# MCU.net
KiCad netlist of a schematic drawn in Altium Designer
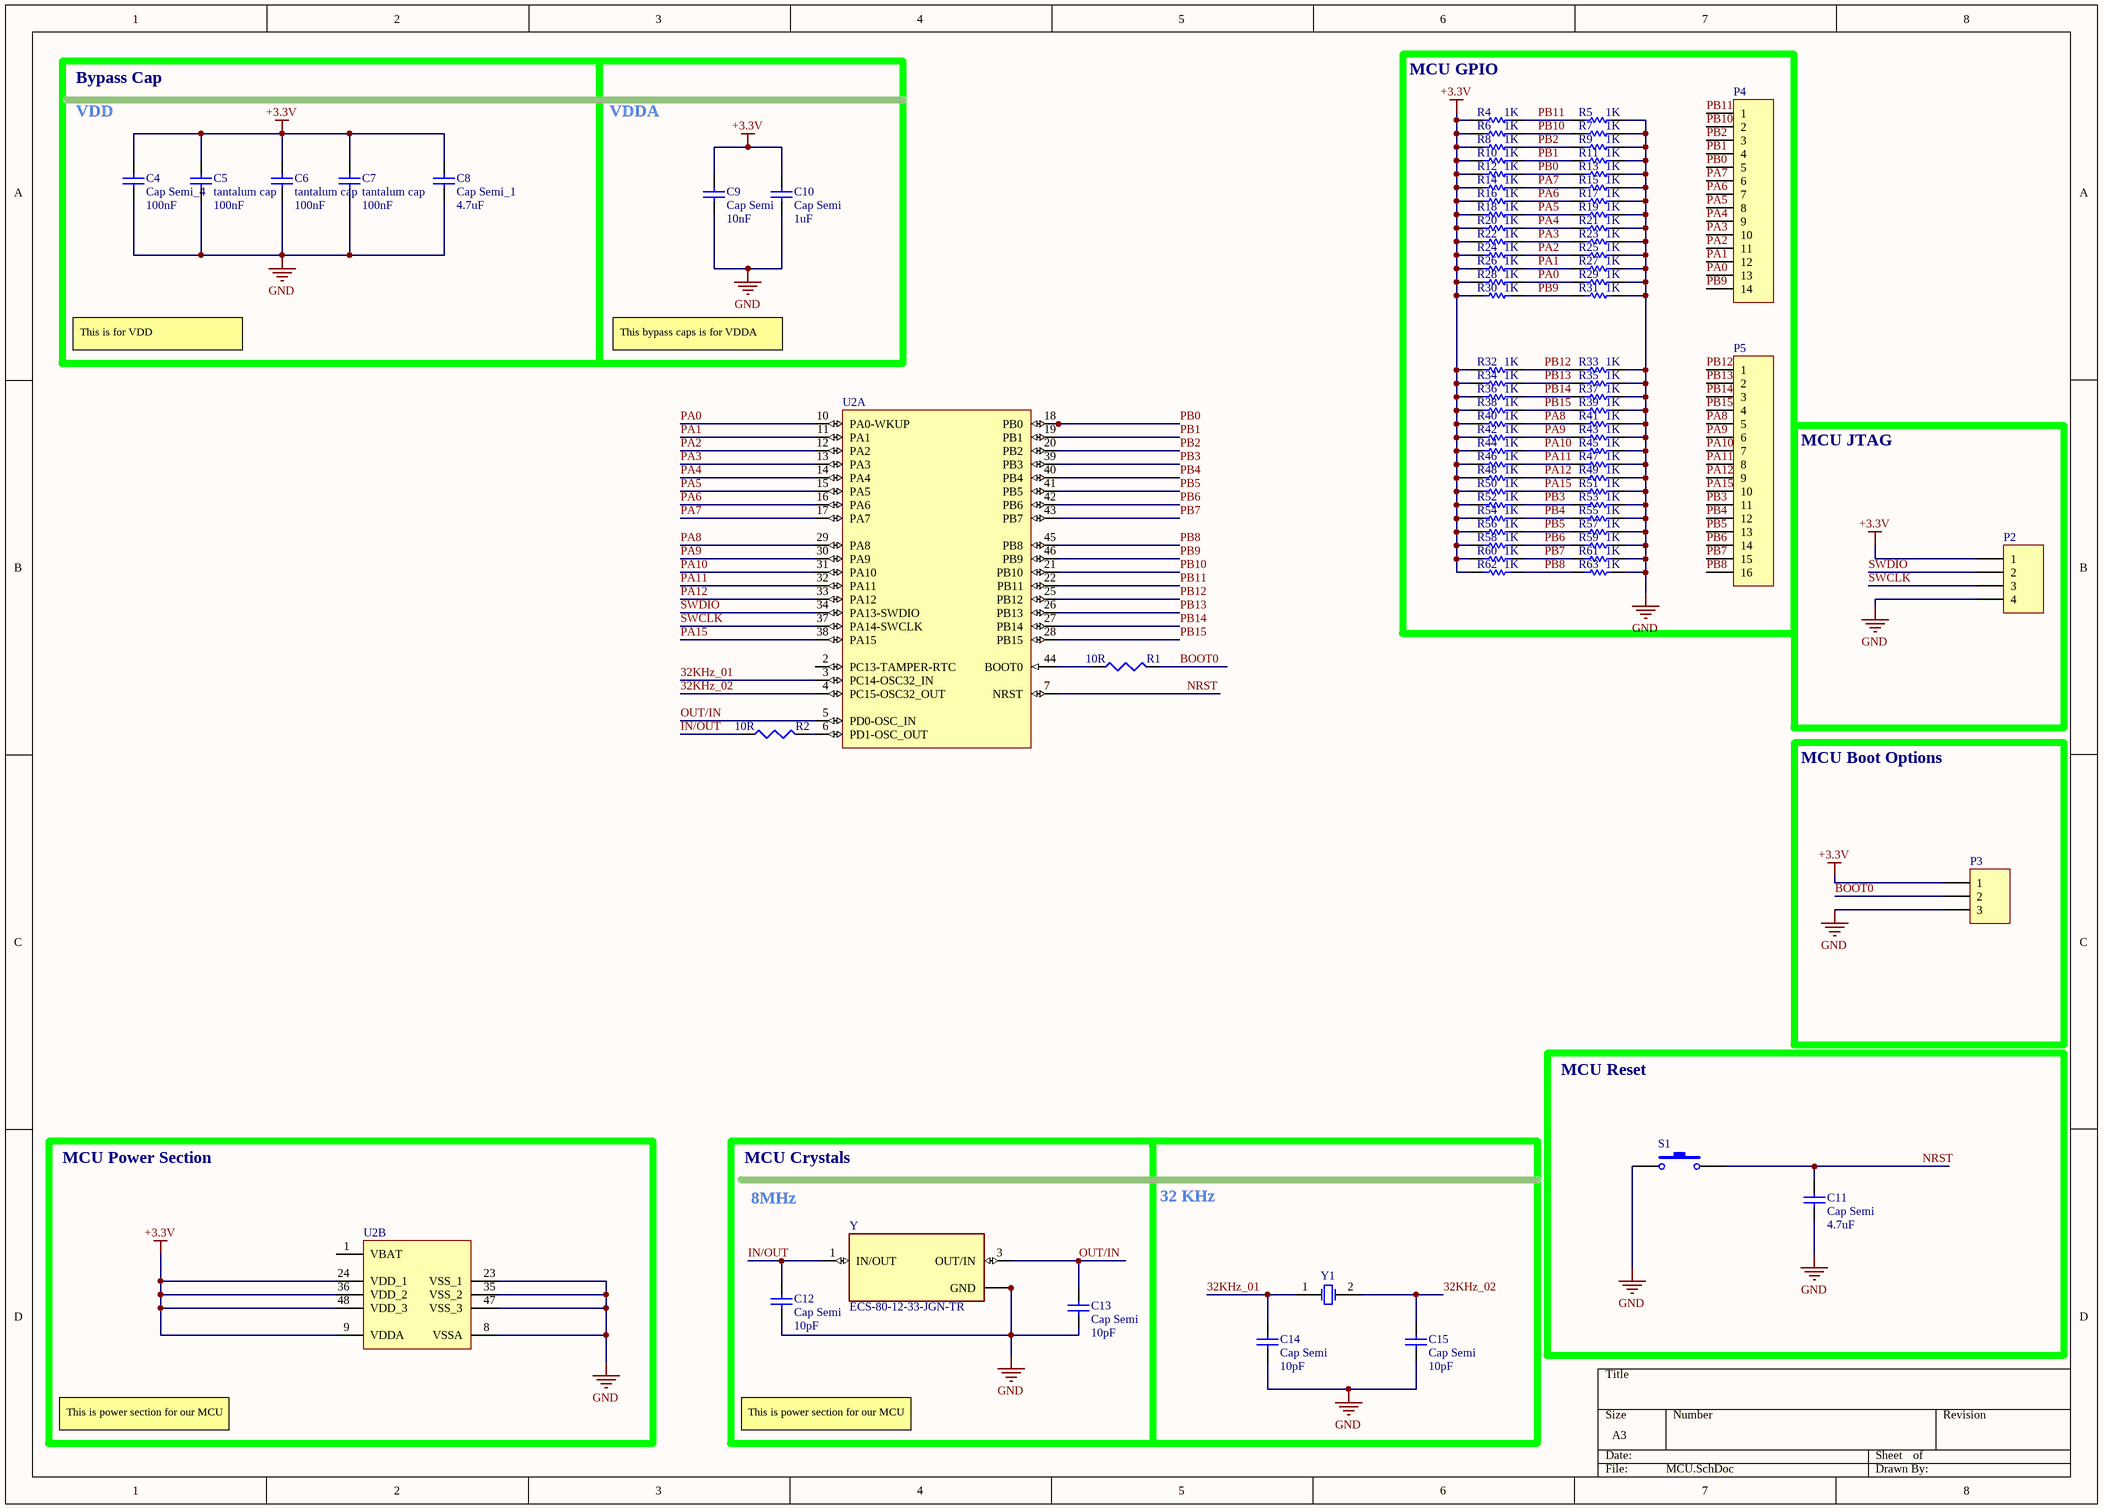
[diagram p0: MCU.SchDoc]

(export (version "E")
  (design (tool "Eeschema 10.0.6"))
  (components
    (comp (ref "C4")
      (value "Cap Semi_4")
      (footprint "0402cap")
      (description "Capacitor (Semiconductor SIM Model)")
      (fields (field (name "ALTIUM_VALUE") "100nF") (field (name "PUBLISHER") "Altium Limited"))
      (libsource (lib "smartmcu(1)") (part "Cap Semi_4"))
    )
    (comp (ref "C5")
      (value "tantalum cap")
      (footprint "C1206tancap")
      (description "Capacitor (Semiconductor SIM Model)")
      (fields (field (name "ALTIUM_VALUE") "100nF") (field (name "PUBLISHER") "Altium Limited"))
      (libsource (lib "smartmcu(1)") (part "Cap Semi_5"))
    )
    (comp (ref "C6")
      (value "tantalum cap")
      (footprint "C1206tancap")
      (description "Capacitor (Semiconductor SIM Model)")
      (fields (field (name "ALTIUM_VALUE") "100nF") (field (name "PUBLISHER") "Altium Limited"))
      (libsource (lib "smartmcu(1)") (part "Cap Semi_6"))
    )
    (comp (ref "C7")
      (value "tantalum cap")
      (footprint "C1206tancap")
      (description "Capacitor (Semiconductor SIM Model)")
      (fields (field (name "ALTIUM_VALUE") "100nF") (field (name "PUBLISHER") "Altium Limited"))
      (libsource (lib "smartmcu(1)") (part "Cap Semi_6"))
    )
    (comp (ref "C8")
      (value "Cap Semi_1")
      (footprint "1608[0603]cap")
      (description "Capacitor (Semiconductor SIM Model)")
      (fields (field (name "ALTIUM_VALUE") "4.7uF") (field (name "PUBLISHER") "Altium Limited"))
      (libsource (lib "smartmcu(1)") (part "Cap Semi_1_1"))
    )
    (comp (ref "C9")
      (value "Cap Semi")
      (footprint "1608[0603]")
      (description "Capacitor (Semiconductor SIM Model)")
      (fields (field (name "ALTIUM_VALUE") "10nF") (field (name "PUBLISHER") "Altium Limited"))
      (libsource (lib "Miscellaneous Devices") (part "Cap Semi"))
    )
    (comp (ref "C10")
      (value "Cap Semi")
      (footprint "1608[0603]")
      (description "Capacitor (Semiconductor SIM Model)")
      (fields (field (name "ALTIUM_VALUE") "1uF") (field (name "PUBLISHER") "Altium Limited"))
      (libsource (lib "Miscellaneous Devices") (part "Cap Semi"))
    )
    (comp (ref "C11")
      (value "Cap Semi")
      (footprint "1608[0603]")
      (description "Capacitor (Semiconductor SIM Model)")
      (fields (field (name "ALTIUM_VALUE") "4.7uF") (field (name "PUBLISHER") "Altium Limited"))
      (libsource (lib "Miscellaneous Devices") (part "Cap Semi"))
    )
    (comp (ref "C12")
      (value "Cap Semi")
      (footprint "0402")
      (description "Capacitor (Semiconductor SIM Model)")
      (fields (field (name "ALTIUM_VALUE") "10pF") (field (name "PUBLISHER") "Altium Limited"))
      (libsource (lib "Miscellaneous Devices") (part "Cap Semi"))
    )
    (comp (ref "C13")
      (value "Cap Semi")
      (footprint "0402")
      (description "Capacitor (Semiconductor SIM Model)")
      (fields (field (name "ALTIUM_VALUE") "10pF") (field (name "PUBLISHER") "Altium Limited"))
      (libsource (lib "Miscellaneous Devices") (part "Cap Semi"))
    )
    (comp (ref "C14")
      (value "Cap Semi")
      (footprint "0402")
      (description "Capacitor (Semiconductor SIM Model)")
      (fields (field (name "ALTIUM_VALUE") "10pF") (field (name "PUBLISHER") "Altium Limited"))
      (libsource (lib "Miscellaneous Devices") (part "Cap Semi"))
    )
    (comp (ref "C15")
      (value "Cap Semi")
      (footprint "0402")
      (description "Capacitor (Semiconductor SIM Model)")
      (fields (field (name "ALTIUM_VALUE") "10pF") (field (name "PUBLISHER") "Altium Limited"))
      (libsource (lib "Miscellaneous Devices") (part "Cap Semi"))
    )
    (comp (ref "P2")
      (value "~")
      (footprint "MHDR1X4")
      (description "Header, 4-Pin")
      (fields (field (name "PUBLISHER") "Altium Limited"))
      (libsource (lib "PCB_Project") (part "MHDR1X4"))
    )
    (comp (ref "P3")
      (value "~")
      (footprint "MHDR1X3")
      (description "Header, 3-Pin")
      (fields (field (name "PUBLISHER") "Altium Limited"))
      (libsource (lib "Miscellaneous Connectors") (part "MHDR1X3"))
    )
    (comp (ref "P4")
      (value "Header 14")
      (footprint "MY_FE14")
      (description "Header, 14-Pin")
      (fields (field (name "ASID PART NUMBER") "Header 14-AS"))
      (libsource (lib "Mylib+Rev+4") (part "Header 14"))
    )
    (comp (ref "P5")
      (value "Header 16")
      (footprint "MY_FE16")
      (description "Header, 16-Pin")
      (fields (field (name "ASID PART NUMBER") "Header 16-AS"))
      (libsource (lib "Mylib+Rev+4") (part "Header 16"))
    )
    (comp (ref "R1")
      (value "10R")
      (footprint "J1-0603")
      (description "Resistor")
      (fields (field (name "Comment") "Res3") (field (name "PUBLISHER") "Altium Limited"))
      (libsource (lib "Miscellaneous Devices") (part "Res3"))
    )
    (comp (ref "R2")
      (value "10R")
      (footprint "J1-0603")
      (description "Resistor")
      (fields (field (name "Comment") "Res3") (field (name "PUBLISHER") "Altium Limited"))
      (libsource (lib "Miscellaneous Devices") (part "Res3"))
    )
    (comp (ref "R4")
      (value "1K")
      (footprint "MY_0603")
      (description "Standard resistor")
      (fields (field (name "ASID PART NUMBER") "Res-AS"))
      (libsource (lib "Mylib+Rev+4") (part "Res"))
    )
    (comp (ref "R5")
      (value "1K")
      (footprint "MY_0603")
      (description "Standard resistor")
      (fields (field (name "ASID PART NUMBER") "Res-AS"))
      (libsource (lib "Mylib+Rev+4") (part "Res"))
    )
    (comp (ref "R6")
      (value "1K")
      (footprint "MY_0603")
      (description "Standard resistor")
      (fields (field (name "ASID PART NUMBER") "Res-AS"))
      (libsource (lib "Mylib+Rev+4") (part "Res"))
    )
    (comp (ref "R7")
      (value "1K")
      (footprint "MY_0603")
      (description "Standard resistor")
      (fields (field (name "ASID PART NUMBER") "Res-AS"))
      (libsource (lib "Mylib+Rev+4") (part "Res"))
    )
    (comp (ref "R8")
      (value "1K")
      (footprint "MY_0603")
      (description "Standard resistor")
      (fields (field (name "ASID PART NUMBER") "Res-AS"))
      (libsource (lib "Mylib+Rev+4") (part "Res"))
    )
    (comp (ref "R9")
      (value "1K")
      (footprint "MY_0603")
      (description "Standard resistor")
      (fields (field (name "ASID PART NUMBER") "Res-AS"))
      (libsource (lib "Mylib+Rev+4") (part "Res"))
    )
    (comp (ref "R10")
      (value "1K")
      (footprint "MY_0603")
      (description "Standard resistor")
      (fields (field (name "ASID PART NUMBER") "Res-AS"))
      (libsource (lib "Mylib+Rev+4") (part "Res"))
    )
    (comp (ref "R11")
      (value "1K")
      (footprint "MY_0603")
      (description "Standard resistor")
      (fields (field (name "ASID PART NUMBER") "Res-AS"))
      (libsource (lib "Mylib+Rev+4") (part "Res"))
    )
    (comp (ref "R12")
      (value "1K")
      (footprint "MY_0603")
      (description "Standard resistor")
      (fields (field (name "ASID PART NUMBER") "Res-AS"))
      (libsource (lib "Mylib+Rev+4") (part "Res"))
    )
    (comp (ref "R13")
      (value "1K")
      (footprint "MY_0603")
      (description "Standard resistor")
      (fields (field (name "ASID PART NUMBER") "Res-AS"))
      (libsource (lib "Mylib+Rev+4") (part "Res"))
    )
    (comp (ref "R14")
      (value "1K")
      (footprint "MY_0603")
      (description "Standard resistor")
      (fields (field (name "ASID PART NUMBER") "Res-AS"))
      (libsource (lib "Mylib+Rev+4") (part "Res"))
    )
    (comp (ref "R15")
      (value "1K")
      (footprint "MY_0603")
      (description "Standard resistor")
      (fields (field (name "ASID PART NUMBER") "Res-AS"))
      (libsource (lib "Mylib+Rev+4") (part "Res"))
    )
    (comp (ref "R16")
      (value "1K")
      (footprint "MY_0603")
      (description "Standard resistor")
      (fields (field (name "ASID PART NUMBER") "Res-AS"))
      (libsource (lib "Mylib+Rev+4") (part "Res"))
    )
    (comp (ref "R17")
      (value "1K")
      (footprint "MY_0603")
      (description "Standard resistor")
      (fields (field (name "ASID PART NUMBER") "Res-AS"))
      (libsource (lib "Mylib+Rev+4") (part "Res"))
    )
    (comp (ref "R18")
      (value "1K")
      (footprint "MY_0603")
      (description "Standard resistor")
      (fields (field (name "ASID PART NUMBER") "Res-AS"))
      (libsource (lib "Mylib+Rev+4") (part "Res"))
    )
    (comp (ref "R19")
      (value "1K")
      (footprint "MY_0603")
      (description "Standard resistor")
      (fields (field (name "ASID PART NUMBER") "Res-AS"))
      (libsource (lib "Mylib+Rev+4") (part "Res"))
    )
    (comp (ref "R20")
      (value "1K")
      (footprint "MY_0603")
      (description "Standard resistor")
      (fields (field (name "ASID PART NUMBER") "Res-AS"))
      (libsource (lib "Mylib+Rev+4") (part "Res"))
    )
    (comp (ref "R21")
      (value "1K")
      (footprint "MY_0603")
      (description "Standard resistor")
      (fields (field (name "ASID PART NUMBER") "Res-AS"))
      (libsource (lib "Mylib+Rev+4") (part "Res"))
    )
    (comp (ref "R22")
      (value "1K")
      (footprint "MY_0603")
      (description "Standard resistor")
      (fields (field (name "ASID PART NUMBER") "Res-AS"))
      (libsource (lib "Mylib+Rev+4") (part "Res"))
    )
    (comp (ref "R23")
      (value "1K")
      (footprint "MY_0603")
      (description "Standard resistor")
      (fields (field (name "ASID PART NUMBER") "Res-AS"))
      (libsource (lib "Mylib+Rev+4") (part "Res"))
    )
    (comp (ref "R24")
      (value "1K")
      (footprint "MY_0603")
      (description "Standard resistor")
      (fields (field (name "ASID PART NUMBER") "Res-AS"))
      (libsource (lib "Mylib+Rev+4") (part "Res"))
    )
    (comp (ref "R25")
      (value "1K")
      (footprint "MY_0603")
      (description "Standard resistor")
      (fields (field (name "ASID PART NUMBER") "Res-AS"))
      (libsource (lib "Mylib+Rev+4") (part "Res"))
    )
    (comp (ref "R26")
      (value "1K")
      (footprint "MY_0603")
      (description "Standard resistor")
      (fields (field (name "ASID PART NUMBER") "Res-AS"))
      (libsource (lib "Mylib+Rev+4") (part "Res"))
    )
    (comp (ref "R27")
      (value "1K")
      (footprint "MY_0603")
      (description "Standard resistor")
      (fields (field (name "ASID PART NUMBER") "Res-AS"))
      (libsource (lib "Mylib+Rev+4") (part "Res"))
    )
    (comp (ref "R28")
      (value "1K")
      (footprint "MY_0603")
      (description "Standard resistor")
      (fields (field (name "ASID PART NUMBER") "Res-AS"))
      (libsource (lib "Mylib+Rev+4") (part "Res"))
    )
    (comp (ref "R29")
      (value "1K")
      (footprint "MY_0603")
      (description "Standard resistor")
      (fields (field (name "ASID PART NUMBER") "Res-AS"))
      (libsource (lib "Mylib+Rev+4") (part "Res"))
    )
    (comp (ref "R30")
      (value "1K")
      (footprint "MY_0603")
      (description "Standard resistor")
      (fields (field (name "ASID PART NUMBER") "Res-AS"))
      (libsource (lib "Mylib+Rev+4") (part "Res"))
    )
    (comp (ref "R31")
      (value "1K")
      (footprint "MY_0603")
      (description "Standard resistor")
      (fields (field (name "ASID PART NUMBER") "Res-AS"))
      (libsource (lib "Mylib+Rev+4") (part "Res"))
    )
    (comp (ref "R32")
      (value "1K")
      (footprint "MY_0603")
      (description "Standard resistor")
      (fields (field (name "ASID PART NUMBER") "Res-AS"))
      (libsource (lib "Mylib+Rev+4") (part "Res"))
    )
    (comp (ref "R33")
      (value "1K")
      (footprint "MY_0603")
      (description "Standard resistor")
      (fields (field (name "ASID PART NUMBER") "Res-AS"))
      (libsource (lib "Mylib+Rev+4") (part "Res"))
    )
    (comp (ref "R34")
      (value "1K")
      (footprint "MY_0603")
      (description "Standard resistor")
      (fields (field (name "ASID PART NUMBER") "Res-AS"))
      (libsource (lib "Mylib+Rev+4") (part "Res"))
    )
    (comp (ref "R35")
      (value "1K")
      (footprint "MY_0603")
      (description "Standard resistor")
      (fields (field (name "ASID PART NUMBER") "Res-AS"))
      (libsource (lib "Mylib+Rev+4") (part "Res"))
    )
    (comp (ref "R36")
      (value "1K")
      (footprint "MY_0603")
      (description "Standard resistor")
      (fields (field (name "ASID PART NUMBER") "Res-AS"))
      (libsource (lib "Mylib+Rev+4") (part "Res"))
    )
    (comp (ref "R37")
      (value "1K")
      (footprint "MY_0603")
      (description "Standard resistor")
      (fields (field (name "ASID PART NUMBER") "Res-AS"))
      (libsource (lib "Mylib+Rev+4") (part "Res"))
    )
    (comp (ref "R38")
      (value "1K")
      (footprint "MY_0603")
      (description "Standard resistor")
      (fields (field (name "ASID PART NUMBER") "Res-AS"))
      (libsource (lib "Mylib+Rev+4") (part "Res"))
    )
    (comp (ref "R39")
      (value "1K")
      (footprint "MY_0603")
      (description "Standard resistor")
      (fields (field (name "ASID PART NUMBER") "Res-AS"))
      (libsource (lib "Mylib+Rev+4") (part "Res"))
    )
    (comp (ref "R40")
      (value "1K")
      (footprint "MY_0603")
      (description "Standard resistor")
      (fields (field (name "ASID PART NUMBER") "Res-AS"))
      (libsource (lib "Mylib+Rev+4") (part "Res"))
    )
    (comp (ref "R41")
      (value "1K")
      (footprint "MY_0603")
      (description "Standard resistor")
      (fields (field (name "ASID PART NUMBER") "Res-AS"))
      (libsource (lib "Mylib+Rev+4") (part "Res"))
    )
    (comp (ref "R42")
      (value "1K")
      (footprint "MY_0603")
      (description "Standard resistor")
      (fields (field (name "ASID PART NUMBER") "Res-AS"))
      (libsource (lib "Mylib+Rev+4") (part "Res"))
    )
    (comp (ref "R43")
      (value "1K")
      (footprint "MY_0603")
      (description "Standard resistor")
      (fields (field (name "ASID PART NUMBER") "Res-AS"))
      (libsource (lib "Mylib+Rev+4") (part "Res"))
    )
    (comp (ref "R44")
      (value "1K")
      (footprint "MY_0603")
      (description "Standard resistor")
      (fields (field (name "ASID PART NUMBER") "Res-AS"))
      (libsource (lib "Mylib+Rev+4") (part "Res"))
    )
    (comp (ref "R45")
      (value "1K")
      (footprint "MY_0603")
      (description "Standard resistor")
      (fields (field (name "ASID PART NUMBER") "Res-AS"))
      (libsource (lib "Mylib+Rev+4") (part "Res"))
    )
    (comp (ref "R46")
      (value "1K")
      (footprint "MY_0603")
      (description "Standard resistor")
      (fields (field (name "ASID PART NUMBER") "Res-AS"))
      (libsource (lib "Mylib+Rev+4") (part "Res"))
    )
    (comp (ref "R47")
      (value "1K")
      (footprint "MY_0603")
      (description "Standard resistor")
      (fields (field (name "ASID PART NUMBER") "Res-AS"))
      (libsource (lib "Mylib+Rev+4") (part "Res"))
    )
    (comp (ref "R48")
      (value "1K")
      (footprint "MY_0603")
      (description "Standard resistor")
      (fields (field (name "ASID PART NUMBER") "Res-AS"))
      (libsource (lib "Mylib+Rev+4") (part "Res"))
    )
    (comp (ref "R49")
      (value "1K")
      (footprint "MY_0603")
      (description "Standard resistor")
      (fields (field (name "ASID PART NUMBER") "Res-AS"))
      (libsource (lib "Mylib+Rev+4") (part "Res"))
    )
    (comp (ref "R50")
      (value "1K")
      (footprint "MY_0603")
      (description "Standard resistor")
      (fields (field (name "ASID PART NUMBER") "Res-AS"))
      (libsource (lib "Mylib+Rev+4") (part "Res"))
    )
    (comp (ref "R51")
      (value "1K")
      (footprint "MY_0603")
      (description "Standard resistor")
      (fields (field (name "ASID PART NUMBER") "Res-AS"))
      (libsource (lib "Mylib+Rev+4") (part "Res"))
    )
    (comp (ref "R52")
      (value "1K")
      (footprint "MY_0603")
      (description "Standard resistor")
      (fields (field (name "ASID PART NUMBER") "Res-AS"))
      (libsource (lib "Mylib+Rev+4") (part "Res"))
    )
    (comp (ref "R53")
      (value "1K")
      (footprint "MY_0603")
      (description "Standard resistor")
      (fields (field (name "ASID PART NUMBER") "Res-AS"))
      (libsource (lib "Mylib+Rev+4") (part "Res"))
    )
    (comp (ref "R54")
      (value "1K")
      (footprint "MY_0603")
      (description "Standard resistor")
      (fields (field (name "ASID PART NUMBER") "Res-AS"))
      (libsource (lib "Mylib+Rev+4") (part "Res"))
    )
    (comp (ref "R55")
      (value "1K")
      (footprint "MY_0603")
      (description "Standard resistor")
      (fields (field (name "ASID PART NUMBER") "Res-AS"))
      (libsource (lib "Mylib+Rev+4") (part "Res"))
    )
    (comp (ref "R56")
      (value "1K")
      (footprint "MY_0603")
      (description "Standard resistor")
      (fields (field (name "ASID PART NUMBER") "Res-AS"))
      (libsource (lib "Mylib+Rev+4") (part "Res"))
    )
    (comp (ref "R57")
      (value "1K")
      (footprint "MY_0603")
      (description "Standard resistor")
      (fields (field (name "ASID PART NUMBER") "Res-AS"))
      (libsource (lib "Mylib+Rev+4") (part "Res"))
    )
    (comp (ref "R58")
      (value "1K")
      (footprint "MY_0603")
      (description "Standard resistor")
      (fields (field (name "ASID PART NUMBER") "Res-AS"))
      (libsource (lib "Mylib+Rev+4") (part "Res"))
    )
    (comp (ref "R59")
      (value "1K")
      (footprint "MY_0603")
      (description "Standard resistor")
      (fields (field (name "ASID PART NUMBER") "Res-AS"))
      (libsource (lib "Mylib+Rev+4") (part "Res"))
    )
    (comp (ref "R60")
      (value "1K")
      (footprint "MY_0603")
      (description "Standard resistor")
      (fields (field (name "ASID PART NUMBER") "Res-AS"))
      (libsource (lib "Mylib+Rev+4") (part "Res"))
    )
    (comp (ref "R61")
      (value "1K")
      (footprint "MY_0603")
      (description "Standard resistor")
      (fields (field (name "ASID PART NUMBER") "Res-AS"))
      (libsource (lib "Mylib+Rev+4") (part "Res"))
    )
    (comp (ref "R62")
      (value "1K")
      (footprint "MY_0603")
      (description "Standard resistor")
      (fields (field (name "ASID PART NUMBER") "Res-AS"))
      (libsource (lib "Mylib+Rev+4") (part "Res"))
    )
    (comp (ref "R63")
      (value "1K")
      (footprint "MY_0603")
      (description "Standard resistor")
      (fields (field (name "ASID PART NUMBER") "Res-AS"))
      (libsource (lib "Mylib+Rev+4") (part "Res"))
    )
    (comp (ref "S1")
      (value "~")
      (footprint "SPST-2")
      (description "Switch")
      (fields (field (name "PUBLISHER") "Altium Limited"))
      (libsource (lib "PCB_Project") (part "SW-PB"))
    )
    (comp (ref "U2")
      (value "~")
      (footprint "STM-LQFP48_M")
      (fields (field (name "PARTNUMBER") "STM32F103C8T6"))
      (libsource (lib "PCB_Project") (part "STM32F103C8T6"))
    )
    (comp (ref "Y")
      (value "ECS-80-12-33-JGN-TR")
      (footprint "XTAL_ECS-240-8-33-AGN-TR")
      (description "8MHz Â±20ppm Crystal 12pF 400 Ohms 4-SMD, No Lead")
      (fields (field (name "MF") "ECS Inc.") (field (name "BUYPART") "h"))
      (libsource (lib "ECS-80-12-33-JGN-TR") (part "ECS-80-12-33-JGN-TR"))
    )
    (comp (ref "Y1")
      (value "~")
      (footprint "R38")
      (description "Crystal Oscillator")
      (fields (field (name "PUBLISHER") "Altium Limited"))
      (libsource (lib "PCB_Project") (part "XTAL"))
    )
  )
  (nets
    (net (code "1") (name "+3.3V") (class "Default")
      (node (ref "C10") (pin "2") (pinfunction "2_2") (pintype "passive"))
      (node (ref "C4") (pin "2") (pinfunction "2_2") (pintype "passive"))
      (node (ref "C5") (pin "2") (pinfunction "2_2") (pintype "passive"))
      (node (ref "C6") (pin "2") (pinfunction "2_2") (pintype "passive"))
      (node (ref "C7") (pin "2") (pinfunction "2_2") (pintype "passive"))
      (node (ref "C8") (pin "2") (pinfunction "2_2") (pintype "passive"))
      (node (ref "C9") (pin "2") (pinfunction "2_2") (pintype "passive"))
      (node (ref "P2") (pin "1") (pinfunction "1_1") (pintype "passive"))
      (node (ref "P3") (pin "1") (pinfunction "1_1") (pintype "passive"))
      (node (ref "R10") (pin "1") (pinfunction "1_1") (pintype "passive"))
      (node (ref "R12") (pin "1") (pinfunction "1_1") (pintype "passive"))
      (node (ref "R14") (pin "1") (pinfunction "1_1") (pintype "passive"))
      (node (ref "R16") (pin "1") (pinfunction "1_1") (pintype "passive"))
      (node (ref "R18") (pin "1") (pinfunction "1_1") (pintype "passive"))
      (node (ref "R20") (pin "1") (pinfunction "1_1") (pintype "passive"))
      (node (ref "R22") (pin "1") (pinfunction "1_1") (pintype "passive"))
      (node (ref "R24") (pin "1") (pinfunction "1_1") (pintype "passive"))
      (node (ref "R26") (pin "1") (pinfunction "1_1") (pintype "passive"))
      (node (ref "R28") (pin "1") (pinfunction "1_1") (pintype "passive"))
      (node (ref "R30") (pin "1") (pinfunction "1_1") (pintype "passive"))
      (node (ref "R32") (pin "1") (pinfunction "1_1") (pintype "passive"))
      (node (ref "R34") (pin "1") (pinfunction "1_1") (pintype "passive"))
      (node (ref "R36") (pin "1") (pinfunction "1_1") (pintype "passive"))
      (node (ref "R38") (pin "1") (pinfunction "1_1") (pintype "passive"))
      (node (ref "R4") (pin "1") (pinfunction "1_1") (pintype "passive"))
      (node (ref "R40") (pin "1") (pinfunction "1_1") (pintype "passive"))
      (node (ref "R42") (pin "1") (pinfunction "1_1") (pintype "passive"))
      (node (ref "R44") (pin "1") (pinfunction "1_1") (pintype "passive"))
      (node (ref "R46") (pin "1") (pinfunction "1_1") (pintype "passive"))
      (node (ref "R48") (pin "1") (pinfunction "1_1") (pintype "passive"))
      (node (ref "R50") (pin "1") (pinfunction "1_1") (pintype "passive"))
      (node (ref "R52") (pin "1") (pinfunction "1_1") (pintype "passive"))
      (node (ref "R54") (pin "1") (pinfunction "1_1") (pintype "passive"))
      (node (ref "R56") (pin "1") (pinfunction "1_1") (pintype "passive"))
      (node (ref "R58") (pin "1") (pinfunction "1_1") (pintype "passive"))
      (node (ref "R6") (pin "1") (pinfunction "1_1") (pintype "passive"))
      (node (ref "R60") (pin "1") (pinfunction "1_1") (pintype "passive"))
      (node (ref "R62") (pin "1") (pinfunction "1_1") (pintype "passive"))
      (node (ref "R8") (pin "1") (pinfunction "1_1") (pintype "passive"))
      (node (ref "U2") (pin "24") (pinfunction "VDD_1_24") (pintype "power_in"))
      (node (ref "U2") (pin "36") (pinfunction "VDD_2_36") (pintype "power_in"))
      (node (ref "U2") (pin "48") (pinfunction "VDD_3_48") (pintype "power_in"))
      (node (ref "U2") (pin "9") (pinfunction "VDDA_9") (pintype "power_in"))
    )
    (net (code "2") (name "/32KHz_01") (class "Default")
      (node (ref "C14") (pin "2") (pinfunction "2_2") (pintype "passive"))
      (node (ref "U2") (pin "3") (pinfunction "PC14-OSC32_IN_3") (pintype "bidirectional"))
      (node (ref "Y1") (pin "1") (pinfunction "OSC1_1") (pintype "passive"))
    )
    (net (code "3") (name "/32KHz_02") (class "Default")
      (node (ref "C15") (pin "2") (pinfunction "2_2") (pintype "passive"))
      (node (ref "U2") (pin "4") (pinfunction "PC15-OSC32_OUT_4") (pintype "bidirectional"))
      (node (ref "Y1") (pin "2") (pinfunction "OSC2_2") (pintype "passive"))
    )
    (net (code "4") (name "/BOOT0") (class "Default")
      (node (ref "P3") (pin "2") (pinfunction "2_2") (pintype "passive"))
      (node (ref "R1") (pin "2") (pinfunction "2_2") (pintype "passive"))
    )
    (net (code "5") (name "/IN{slash}OUT") (class "Default")
      (node (ref "C12") (pin "2") (pinfunction "2_2") (pintype "passive"))
      (node (ref "R2") (pin "1") (pinfunction "1_1") (pintype "passive"))
      (node (ref "Y") (pin "1") (pinfunction "IN/OUT_1") (pintype "bidirectional"))
    )
    (net (code "6") (name "/NRST") (class "Default")
      (node (ref "C11") (pin "2") (pinfunction "2_2") (pintype "passive"))
      (node (ref "S1") (pin "2") (pinfunction "2_2") (pintype "passive"))
      (node (ref "U2") (pin "7") (pinfunction "NRST_7") (pintype "bidirectional"))
    )
    (net (code "7") (name "/OUT{slash}IN") (class "Default")
      (node (ref "C13") (pin "2") (pinfunction "2_2") (pintype "passive"))
      (node (ref "U2") (pin "5") (pinfunction "PD0-OSC_IN_5") (pintype "bidirectional"))
      (node (ref "Y") (pin "3") (pinfunction "OUT/IN_3") (pintype "bidirectional"))
    )
    (net (code "8") (name "/PA0") (class "Default")
      (node (ref "P4") (pin "13") (pinfunction "13_13") (pintype "passive"))
      (node (ref "R28") (pin "2") (pinfunction "2_2") (pintype "passive"))
      (node (ref "R29") (pin "1") (pinfunction "1_1") (pintype "passive"))
      (node (ref "U2") (pin "10") (pinfunction "PA0-WKUP_10") (pintype "bidirectional"))
    )
    (net (code "9") (name "/PA1") (class "Default")
      (node (ref "P4") (pin "12") (pinfunction "12_12") (pintype "passive"))
      (node (ref "R26") (pin "2") (pinfunction "2_2") (pintype "passive"))
      (node (ref "R27") (pin "1") (pinfunction "1_1") (pintype "passive"))
      (node (ref "U2") (pin "11") (pinfunction "PA1_11") (pintype "bidirectional"))
    )
    (net (code "10") (name "/PA2") (class "Default")
      (node (ref "P4") (pin "11") (pinfunction "11_11") (pintype "passive"))
      (node (ref "R24") (pin "2") (pinfunction "2_2") (pintype "passive"))
      (node (ref "R25") (pin "1") (pinfunction "1_1") (pintype "passive"))
      (node (ref "U2") (pin "12") (pinfunction "PA2_12") (pintype "bidirectional"))
    )
    (net (code "11") (name "/PA3") (class "Default")
      (node (ref "P4") (pin "10") (pinfunction "10_10") (pintype "passive"))
      (node (ref "R22") (pin "2") (pinfunction "2_2") (pintype "passive"))
      (node (ref "R23") (pin "1") (pinfunction "1_1") (pintype "passive"))
      (node (ref "U2") (pin "13") (pinfunction "PA3_13") (pintype "bidirectional"))
    )
    (net (code "12") (name "/PA4") (class "Default")
      (node (ref "P4") (pin "9") (pinfunction "9_9") (pintype "passive"))
      (node (ref "R20") (pin "2") (pinfunction "2_2") (pintype "passive"))
      (node (ref "R21") (pin "1") (pinfunction "1_1") (pintype "passive"))
      (node (ref "U2") (pin "14") (pinfunction "PA4_14") (pintype "bidirectional"))
    )
    (net (code "13") (name "/PA5") (class "Default")
      (node (ref "P4") (pin "8") (pinfunction "8_8") (pintype "passive"))
      (node (ref "R18") (pin "2") (pinfunction "2_2") (pintype "passive"))
      (node (ref "R19") (pin "1") (pinfunction "1_1") (pintype "passive"))
      (node (ref "U2") (pin "15") (pinfunction "PA5_15") (pintype "bidirectional"))
    )
    (net (code "14") (name "/PA6") (class "Default")
      (node (ref "P4") (pin "7") (pinfunction "7_7") (pintype "passive"))
      (node (ref "R16") (pin "2") (pinfunction "2_2") (pintype "passive"))
      (node (ref "R17") (pin "1") (pinfunction "1_1") (pintype "passive"))
      (node (ref "U2") (pin "16") (pinfunction "PA6_16") (pintype "bidirectional"))
    )
    (net (code "15") (name "/PA7") (class "Default")
      (node (ref "P4") (pin "6") (pinfunction "6_6") (pintype "passive"))
      (node (ref "R14") (pin "2") (pinfunction "2_2") (pintype "passive"))
      (node (ref "R15") (pin "1") (pinfunction "1_1") (pintype "passive"))
      (node (ref "U2") (pin "17") (pinfunction "PA7_17") (pintype "bidirectional"))
    )
    (net (code "16") (name "/PA8") (class "Default")
      (node (ref "P5") (pin "5") (pinfunction "5_5") (pintype "passive"))
      (node (ref "R40") (pin "2") (pinfunction "2_2") (pintype "passive"))
      (node (ref "R41") (pin "1") (pinfunction "1_1") (pintype "passive"))
      (node (ref "U2") (pin "29") (pinfunction "PA8_29") (pintype "bidirectional"))
    )
    (net (code "17") (name "/PA9") (class "Default")
      (node (ref "P5") (pin "6") (pinfunction "6_6") (pintype "passive"))
      (node (ref "R42") (pin "2") (pinfunction "2_2") (pintype "passive"))
      (node (ref "R43") (pin "1") (pinfunction "1_1") (pintype "passive"))
      (node (ref "U2") (pin "30") (pinfunction "PA9_30") (pintype "bidirectional"))
    )
    (net (code "18") (name "/PA10") (class "Default")
      (node (ref "P5") (pin "7") (pinfunction "7_7") (pintype "passive"))
      (node (ref "R44") (pin "2") (pinfunction "2_2") (pintype "passive"))
      (node (ref "R45") (pin "1") (pinfunction "1_1") (pintype "passive"))
      (node (ref "U2") (pin "31") (pinfunction "PA10_31") (pintype "bidirectional"))
    )
    (net (code "19") (name "/PA11") (class "Default")
      (node (ref "P5") (pin "8") (pinfunction "8_8") (pintype "passive"))
      (node (ref "R46") (pin "2") (pinfunction "2_2") (pintype "passive"))
      (node (ref "R47") (pin "1") (pinfunction "1_1") (pintype "passive"))
      (node (ref "U2") (pin "32") (pinfunction "PA11_32") (pintype "bidirectional"))
    )
    (net (code "20") (name "/PA12") (class "Default")
      (node (ref "P5") (pin "9") (pinfunction "9_9") (pintype "passive"))
      (node (ref "R48") (pin "2") (pinfunction "2_2") (pintype "passive"))
      (node (ref "R49") (pin "1") (pinfunction "1_1") (pintype "passive"))
      (node (ref "U2") (pin "33") (pinfunction "PA12_33") (pintype "bidirectional"))
    )
    (net (code "21") (name "/PA15") (class "Default")
      (node (ref "P5") (pin "10") (pinfunction "10_10") (pintype "passive"))
      (node (ref "R50") (pin "2") (pinfunction "2_2") (pintype "passive"))
      (node (ref "R51") (pin "1") (pinfunction "1_1") (pintype "passive"))
      (node (ref "U2") (pin "38") (pinfunction "PA15_38") (pintype "bidirectional"))
    )
    (net (code "22") (name "/PB0") (class "Default")
      (node (ref "P4") (pin "5") (pinfunction "5_5") (pintype "passive"))
      (node (ref "R12") (pin "2") (pinfunction "2_2") (pintype "passive"))
      (node (ref "R13") (pin "1") (pinfunction "1_1") (pintype "passive"))
      (node (ref "U2") (pin "18") (pinfunction "PB0_18") (pintype "bidirectional"))
    )
    (net (code "23") (name "/PB1") (class "Default")
      (node (ref "P4") (pin "4") (pinfunction "4_4") (pintype "passive"))
      (node (ref "R10") (pin "2") (pinfunction "2_2") (pintype "passive"))
      (node (ref "R11") (pin "1") (pinfunction "1_1") (pintype "passive"))
      (node (ref "U2") (pin "19") (pinfunction "PB1_19") (pintype "bidirectional"))
    )
    (net (code "24") (name "/PB2") (class "Default")
      (node (ref "P4") (pin "3") (pinfunction "3_3") (pintype "passive"))
      (node (ref "R8") (pin "2") (pinfunction "2_2") (pintype "passive"))
      (node (ref "R9") (pin "1") (pinfunction "1_1") (pintype "passive"))
      (node (ref "U2") (pin "20") (pinfunction "PB2_20") (pintype "bidirectional"))
    )
    (net (code "25") (name "/PB3") (class "Default")
      (node (ref "P5") (pin "11") (pinfunction "11_11") (pintype "passive"))
      (node (ref "R52") (pin "2") (pinfunction "2_2") (pintype "passive"))
      (node (ref "R53") (pin "1") (pinfunction "1_1") (pintype "passive"))
      (node (ref "U2") (pin "39") (pinfunction "PB3_39") (pintype "bidirectional"))
    )
    (net (code "26") (name "/PB4") (class "Default")
      (node (ref "P5") (pin "12") (pinfunction "12_12") (pintype "passive"))
      (node (ref "R54") (pin "2") (pinfunction "2_2") (pintype "passive"))
      (node (ref "R55") (pin "1") (pinfunction "1_1") (pintype "passive"))
      (node (ref "U2") (pin "40") (pinfunction "PB4_40") (pintype "bidirectional"))
    )
    (net (code "27") (name "/PB5") (class "Default")
      (node (ref "P5") (pin "13") (pinfunction "13_13") (pintype "passive"))
      (node (ref "R56") (pin "2") (pinfunction "2_2") (pintype "passive"))
      (node (ref "R57") (pin "1") (pinfunction "1_1") (pintype "passive"))
      (node (ref "U2") (pin "41") (pinfunction "PB5_41") (pintype "bidirectional"))
    )
    (net (code "28") (name "/PB6") (class "Default")
      (node (ref "P5") (pin "14") (pinfunction "14_14") (pintype "passive"))
      (node (ref "R58") (pin "2") (pinfunction "2_2") (pintype "passive"))
      (node (ref "R59") (pin "1") (pinfunction "1_1") (pintype "passive"))
      (node (ref "U2") (pin "42") (pinfunction "PB6_42") (pintype "bidirectional"))
    )
    (net (code "29") (name "/PB7") (class "Default")
      (node (ref "P5") (pin "15") (pinfunction "15_15") (pintype "passive"))
      (node (ref "R60") (pin "2") (pinfunction "2_2") (pintype "passive"))
      (node (ref "R61") (pin "1") (pinfunction "1_1") (pintype "passive"))
      (node (ref "U2") (pin "43") (pinfunction "PB7_43") (pintype "bidirectional"))
    )
    (net (code "30") (name "/PB8") (class "Default")
      (node (ref "P5") (pin "16") (pinfunction "16_16") (pintype "passive"))
      (node (ref "R62") (pin "2") (pinfunction "2_2") (pintype "passive"))
      (node (ref "R63") (pin "1") (pinfunction "1_1") (pintype "passive"))
      (node (ref "U2") (pin "45") (pinfunction "PB8_45") (pintype "bidirectional"))
    )
    (net (code "31") (name "/PB9") (class "Default")
      (node (ref "P4") (pin "14") (pinfunction "14_14") (pintype "passive"))
      (node (ref "R30") (pin "2") (pinfunction "2_2") (pintype "passive"))
      (node (ref "R31") (pin "1") (pinfunction "1_1") (pintype "passive"))
      (node (ref "U2") (pin "46") (pinfunction "PB9_46") (pintype "bidirectional"))
    )
    (net (code "32") (name "/PB10") (class "Default")
      (node (ref "P4") (pin "2") (pinfunction "2_2") (pintype "passive"))
      (node (ref "R6") (pin "2") (pinfunction "2_2") (pintype "passive"))
      (node (ref "R7") (pin "1") (pinfunction "1_1") (pintype "passive"))
      (node (ref "U2") (pin "21") (pinfunction "PB10_21") (pintype "bidirectional"))
    )
    (net (code "33") (name "/PB11") (class "Default")
      (node (ref "P4") (pin "1") (pinfunction "1_1") (pintype "passive"))
      (node (ref "R4") (pin "2") (pinfunction "2_2") (pintype "passive"))
      (node (ref "R5") (pin "1") (pinfunction "1_1") (pintype "passive"))
      (node (ref "U2") (pin "22") (pinfunction "PB11_22") (pintype "bidirectional"))
    )
    (net (code "34") (name "/PB12") (class "Default")
      (node (ref "P5") (pin "1") (pinfunction "1_1") (pintype "passive"))
      (node (ref "R32") (pin "2") (pinfunction "2_2") (pintype "passive"))
      (node (ref "R33") (pin "1") (pinfunction "1_1") (pintype "passive"))
      (node (ref "U2") (pin "25") (pinfunction "PB12_25") (pintype "bidirectional"))
    )
    (net (code "35") (name "/PB13") (class "Default")
      (node (ref "P5") (pin "2") (pinfunction "2_2") (pintype "passive"))
      (node (ref "R34") (pin "2") (pinfunction "2_2") (pintype "passive"))
      (node (ref "R35") (pin "1") (pinfunction "1_1") (pintype "passive"))
      (node (ref "U2") (pin "26") (pinfunction "PB13_26") (pintype "bidirectional"))
    )
    (net (code "36") (name "/PB14") (class "Default")
      (node (ref "P5") (pin "3") (pinfunction "3_3") (pintype "passive"))
      (node (ref "R36") (pin "2") (pinfunction "2_2") (pintype "passive"))
      (node (ref "R37") (pin "1") (pinfunction "1_1") (pintype "passive"))
      (node (ref "U2") (pin "27") (pinfunction "PB14_27") (pintype "bidirectional"))
    )
    (net (code "37") (name "/PB15") (class "Default")
      (node (ref "P5") (pin "4") (pinfunction "4_4") (pintype "passive"))
      (node (ref "R38") (pin "2") (pinfunction "2_2") (pintype "passive"))
      (node (ref "R39") (pin "1") (pinfunction "1_1") (pintype "passive"))
      (node (ref "U2") (pin "28") (pinfunction "PB15_28") (pintype "bidirectional"))
    )
    (net (code "38") (name "/SWCLK") (class "Default")
      (node (ref "P2") (pin "3") (pinfunction "3_3") (pintype "passive"))
      (node (ref "U2") (pin "37") (pinfunction "PA14-SWCLK_37") (pintype "bidirectional"))
    )
    (net (code "39") (name "/SWDIO") (class "Default")
      (node (ref "P2") (pin "2") (pinfunction "2_2") (pintype "passive"))
      (node (ref "U2") (pin "34") (pinfunction "PA13-SWDIO_34") (pintype "bidirectional"))
    )
    (net (code "40") (name "GND") (class "Default")
      (node (ref "C10") (pin "1") (pinfunction "1_1") (pintype "passive"))
      (node (ref "C11") (pin "1") (pinfunction "1_1") (pintype "passive"))
      (node (ref "C12") (pin "1") (pinfunction "1_1") (pintype "passive"))
      (node (ref "C13") (pin "1") (pinfunction "1_1") (pintype "passive"))
      (node (ref "C14") (pin "1") (pinfunction "1_1") (pintype "passive"))
      (node (ref "C15") (pin "1") (pinfunction "1_1") (pintype "passive"))
      (node (ref "C4") (pin "1") (pinfunction "1_1") (pintype "passive"))
      (node (ref "C5") (pin "1") (pinfunction "1_1") (pintype "passive"))
      (node (ref "C6") (pin "1") (pinfunction "1_1") (pintype "passive"))
      (node (ref "C7") (pin "1") (pinfunction "1_1") (pintype "passive"))
      (node (ref "C8") (pin "1") (pinfunction "1_1") (pintype "passive"))
      (node (ref "C9") (pin "1") (pinfunction "1_1") (pintype "passive"))
      (node (ref "P2") (pin "4") (pinfunction "4_4") (pintype "passive"))
      (node (ref "P3") (pin "3") (pinfunction "3_3") (pintype "passive"))
      (node (ref "R11") (pin "2") (pinfunction "2_2") (pintype "passive"))
      (node (ref "R13") (pin "2") (pinfunction "2_2") (pintype "passive"))
      (node (ref "R15") (pin "2") (pinfunction "2_2") (pintype "passive"))
      (node (ref "R17") (pin "2") (pinfunction "2_2") (pintype "passive"))
      (node (ref "R19") (pin "2") (pinfunction "2_2") (pintype "passive"))
      (node (ref "R21") (pin "2") (pinfunction "2_2") (pintype "passive"))
      (node (ref "R23") (pin "2") (pinfunction "2_2") (pintype "passive"))
      (node (ref "R25") (pin "2") (pinfunction "2_2") (pintype "passive"))
      (node (ref "R27") (pin "2") (pinfunction "2_2") (pintype "passive"))
      (node (ref "R29") (pin "2") (pinfunction "2_2") (pintype "passive"))
      (node (ref "R31") (pin "2") (pinfunction "2_2") (pintype "passive"))
      (node (ref "R33") (pin "2") (pinfunction "2_2") (pintype "passive"))
      (node (ref "R35") (pin "2") (pinfunction "2_2") (pintype "passive"))
      (node (ref "R37") (pin "2") (pinfunction "2_2") (pintype "passive"))
      (node (ref "R39") (pin "2") (pinfunction "2_2") (pintype "passive"))
      (node (ref "R41") (pin "2") (pinfunction "2_2") (pintype "passive"))
      (node (ref "R43") (pin "2") (pinfunction "2_2") (pintype "passive"))
      (node (ref "R45") (pin "2") (pinfunction "2_2") (pintype "passive"))
      (node (ref "R47") (pin "2") (pinfunction "2_2") (pintype "passive"))
      (node (ref "R49") (pin "2") (pinfunction "2_2") (pintype "passive"))
      (node (ref "R5") (pin "2") (pinfunction "2_2") (pintype "passive"))
      (node (ref "R51") (pin "2") (pinfunction "2_2") (pintype "passive"))
      (node (ref "R53") (pin "2") (pinfunction "2_2") (pintype "passive"))
      (node (ref "R55") (pin "2") (pinfunction "2_2") (pintype "passive"))
      (node (ref "R57") (pin "2") (pinfunction "2_2") (pintype "passive"))
      (node (ref "R59") (pin "2") (pinfunction "2_2") (pintype "passive"))
      (node (ref "R61") (pin "2") (pinfunction "2_2") (pintype "passive"))
      (node (ref "R63") (pin "2") (pinfunction "2_2") (pintype "passive"))
      (node (ref "R7") (pin "2") (pinfunction "2_2") (pintype "passive"))
      (node (ref "R9") (pin "2") (pinfunction "2_2") (pintype "passive"))
      (node (ref "S1") (pin "1") (pinfunction "1_1") (pintype "passive"))
      (node (ref "U2") (pin "23") (pinfunction "VSS_1_23") (pintype "power_in"))
      (node (ref "U2") (pin "35") (pinfunction "VSS_2_35") (pintype "power_in"))
      (node (ref "U2") (pin "47") (pinfunction "VSS_3_47") (pintype "power_in"))
      (node (ref "U2") (pin "8") (pinfunction "VSSA_8") (pintype "power_in"))
      (node (ref "Y") (pin "2") (pinfunction "GND_2") (pintype "power_in"))
      (node (ref "Y") (pin "4") (pinfunction "GND_4") (pintype "power_in"))
    )
    (net (code "41") (name "Net-(U2A-BOOT0)") (class "Default")
      (node (ref "R1") (pin "1") (pinfunction "1_1") (pintype "passive"))
      (node (ref "U2") (pin "44") (pinfunction "BOOT0_44") (pintype "input"))
    )
    (net (code "42") (name "Net-(U2A-PD1-OSC_OUT)") (class "Default")
      (node (ref "R2") (pin "2") (pinfunction "2_2") (pintype "passive"))
      (node (ref "U2") (pin "6") (pinfunction "PD1-OSC_OUT_6") (pintype "bidirectional"))
    )
    (net (code "43") (name "unconnected-(U2A-PC13-TAMPER-RTC-Pad2)") (class "Default")
      (node (ref "U2") (pin "2") (pinfunction "PC13-TAMPER-RTC_2") (pintype "bidirectional"))
    )
    (net (code "44") (name "unconnected-(U2B-VBAT-Pad1)") (class "Default")
      (node (ref "U2") (pin "1") (pinfunction "VBAT_1") (pintype "power_in"))
    )
  )
)
